# ppt_full_charger_f1.net
KiCad netlist of a schematic drawn in EAGLE
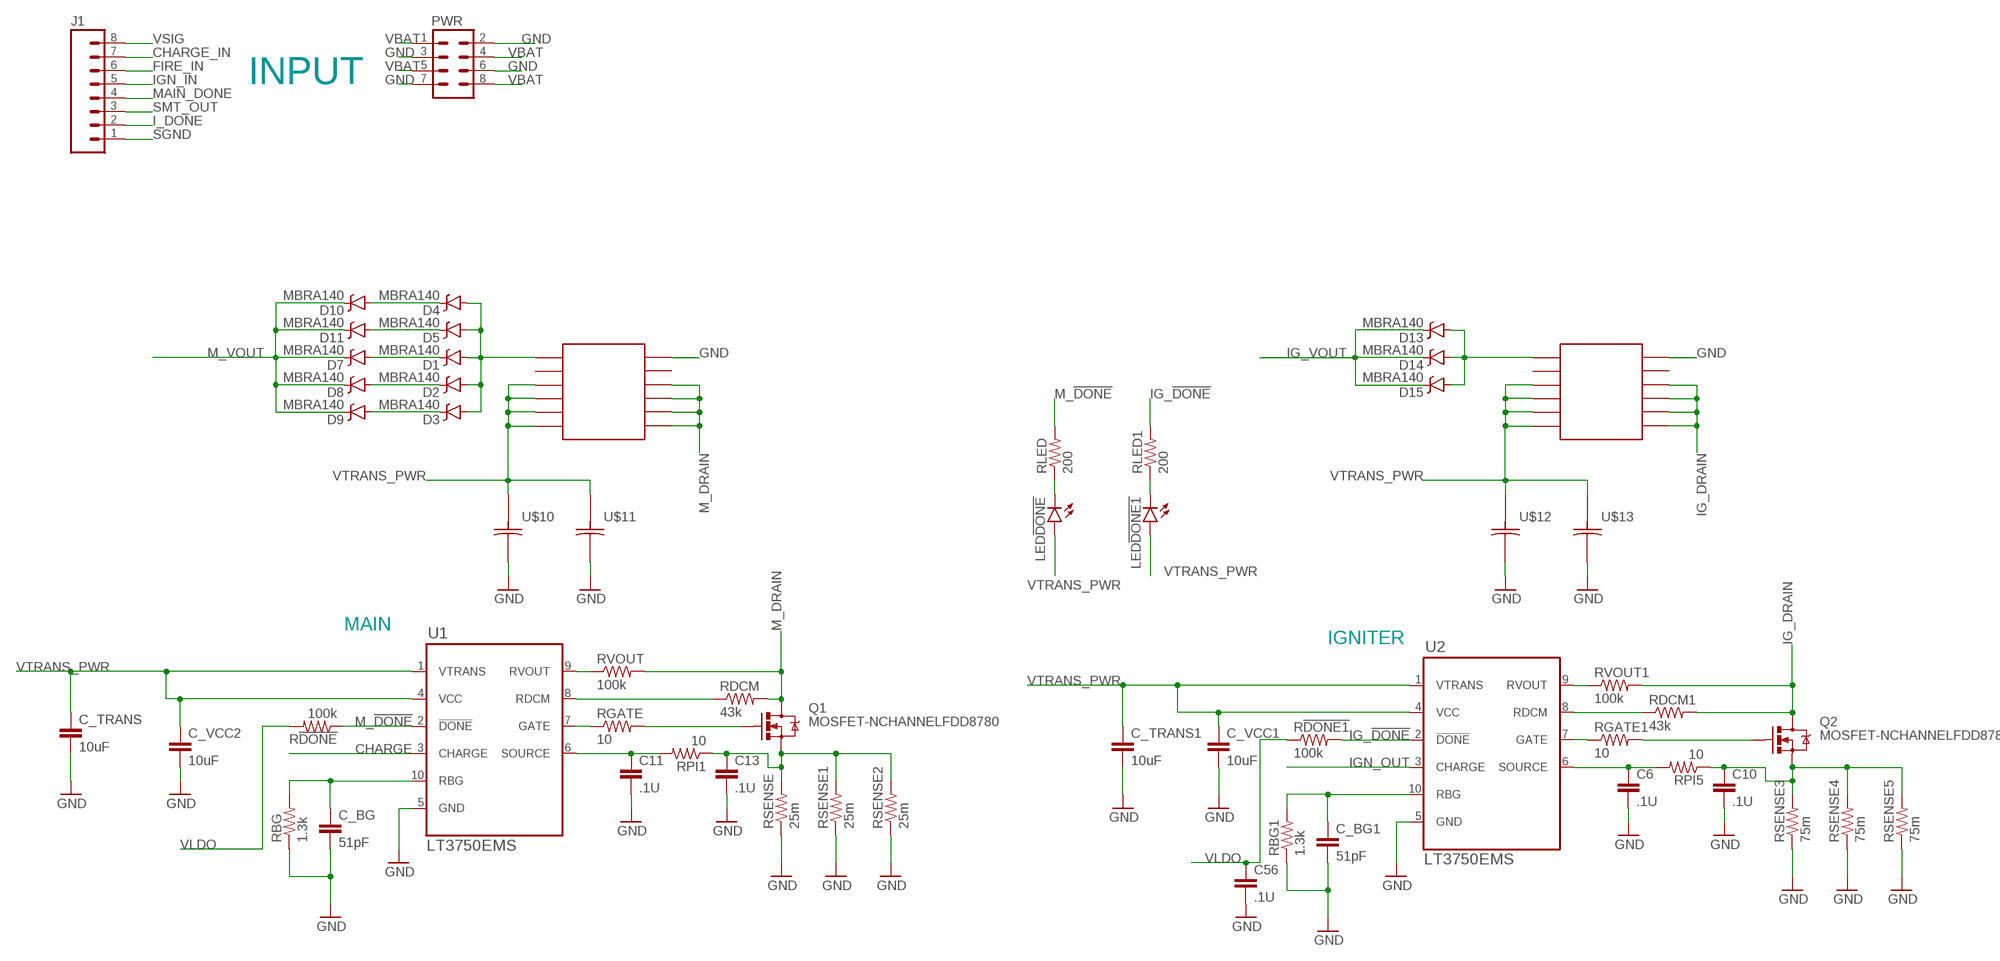
[diagram p0: schematic, sheet 1]
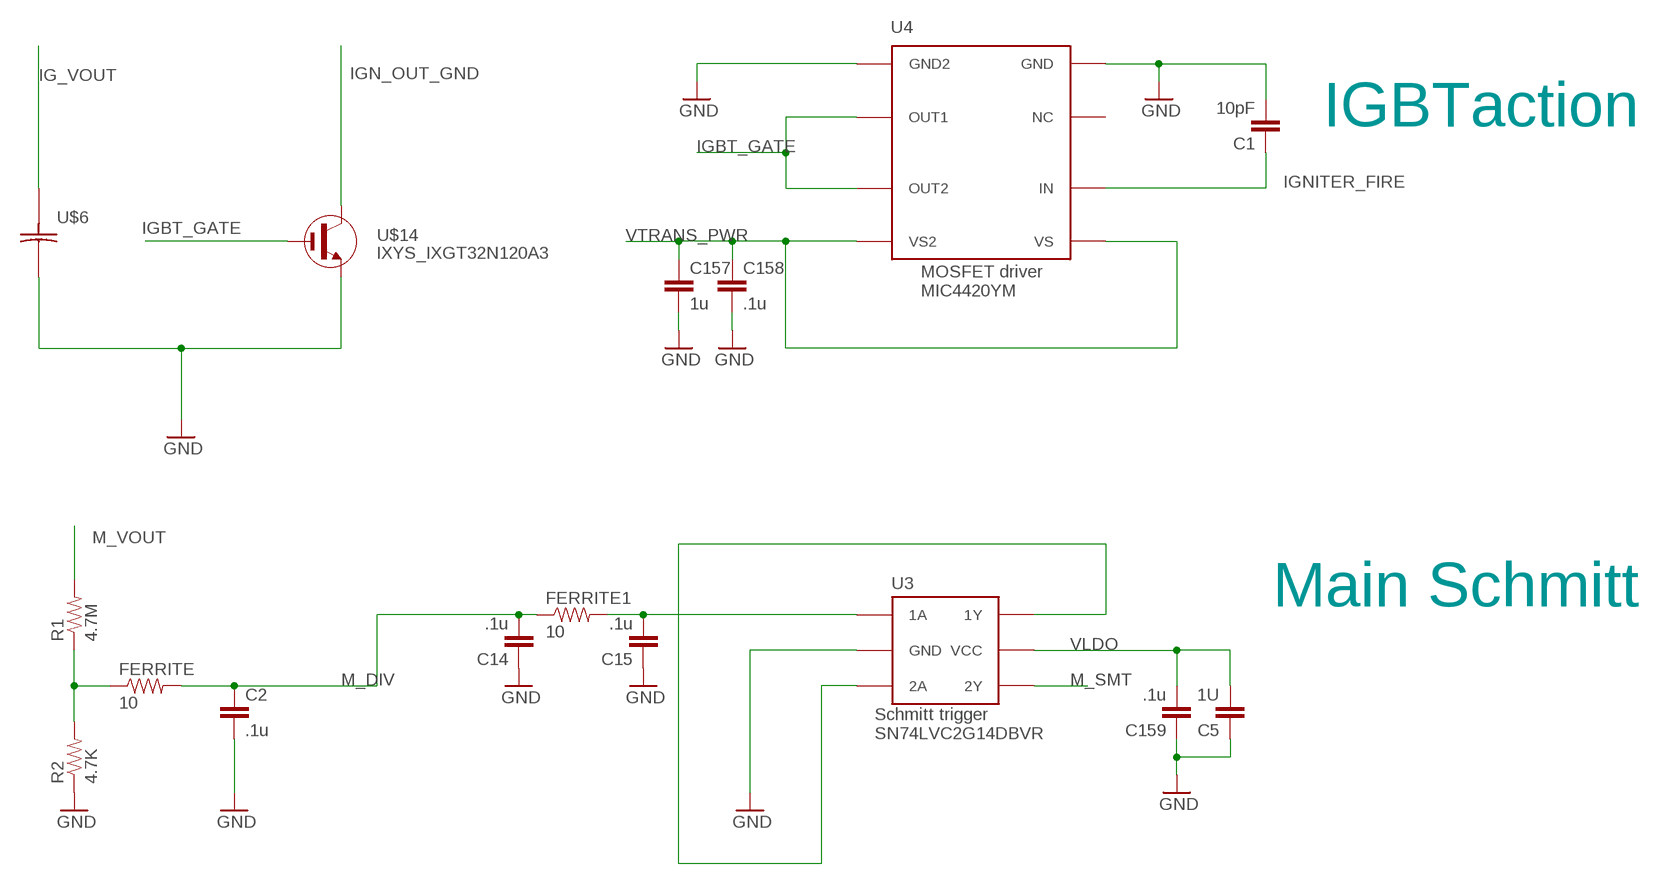
[diagram p1: schematic, sheet 2]
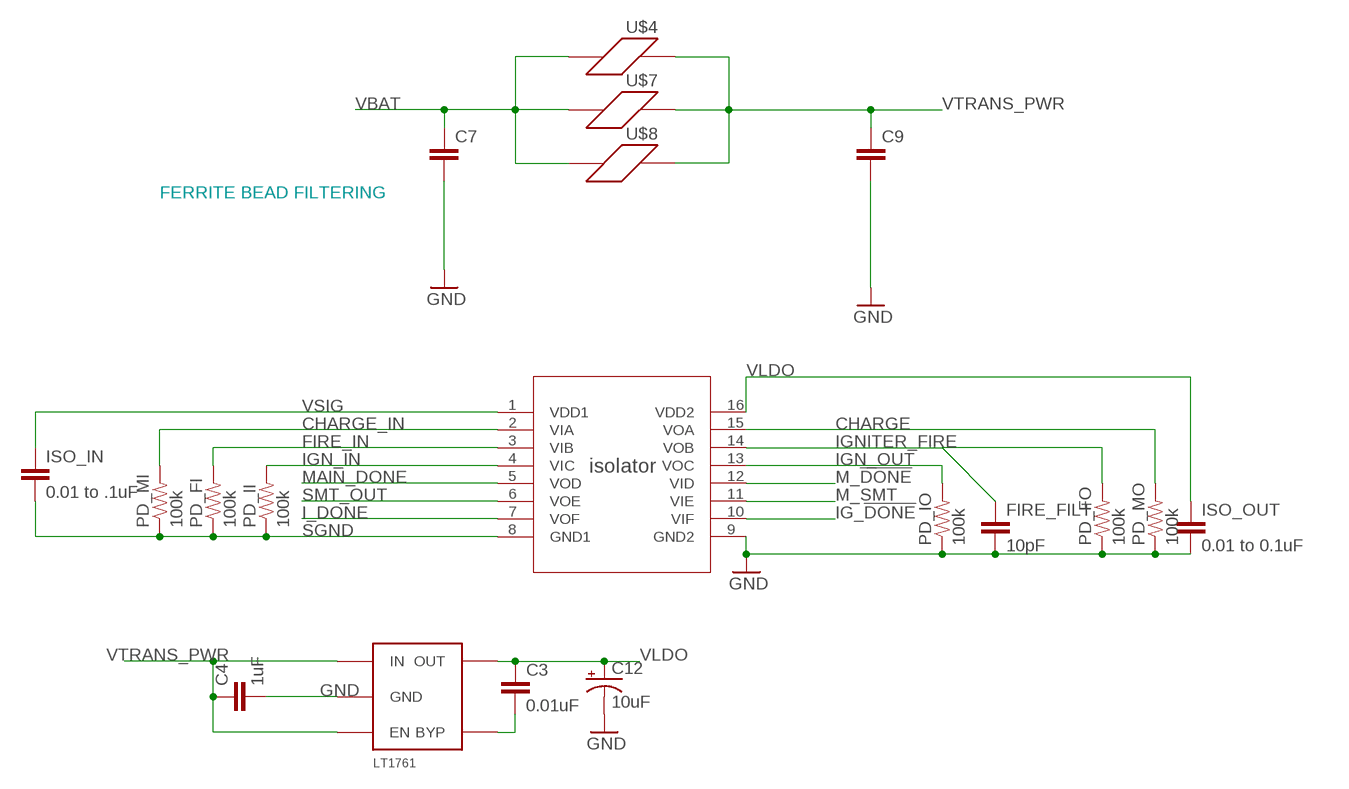
[diagram p2: schematic, sheet 3]

(export (version "E")
  (design (tool "Eeschema 10.0.6"))
  (components
    (comp (ref "ADUM163N")
      (value "ADUM163N1BRZ")
      (footprint "eagle-import:R_16")
      (libsource (lib "eagle-import") (part "ADUM163N1BRZ"))
    )
    (comp (ref "C3")
      (value "0.01uF")
      (footprint "eagle-import:0805")
      (libsource (lib "eagle-import") (part "SparkFun-Passives_CAP0805"))
    )
    (comp (ref "C4")
      (value "1uF")
      (footprint "eagle-import:0805")
      (libsource (lib "eagle-import") (part "SparkFun-Passives_CAP0805"))
    )
    (comp (ref "C7")
      (value "CAP0805")
      (footprint "eagle-import:0805")
      (libsource (lib "eagle-import") (part "CAP0805"))
    )
    (comp (ref "C9")
      (value "CAP0805")
      (footprint "eagle-import:0805")
      (libsource (lib "eagle-import") (part "CAP0805"))
    )
    (comp (ref "C12")
      (value "10uF")
      (footprint "eagle-import:EIA3216")
      (libsource (lib "eagle-import") (part "10UF-TANT"))
    )
    (comp (ref "FIRE_FILT")
      (value "10pF")
      (footprint "eagle-import:0805")
      (libsource (lib "eagle-import") (part "SparkFun-Passives_CAP0805"))
    )
    (comp (ref "ISO_IN")
      (value "0.01 to .1uF")
      (footprint "eagle-import:0805")
      (libsource (lib "eagle-import") (part "SparkFun-Passives_CAP0805"))
    )
    (comp (ref "ISO_OUT")
      (value "0.01 to 0.1uF")
      (footprint "eagle-import:0805")
      (libsource (lib "eagle-import") (part "SparkFun-Passives_CAP0805"))
    )
    (comp (ref "LDO")
      (value "LINEAR_LDO_LT1761-X")
      (footprint "eagle-import:SOT-23-5")
      (libsource (lib "eagle-import") (part "LINEAR_LDO_LT1761-X"))
    )
    (comp (ref "PD_FI")
      (value "100k")
      (footprint "eagle-import:0805")
      (libsource (lib "eagle-import") (part "RESISTOR0805-RES"))
    )
    (comp (ref "PD_FO")
      (value "100k")
      (footprint "eagle-import:0805")
      (libsource (lib "eagle-import") (part "RESISTOR0805-RES"))
    )
    (comp (ref "PD_II")
      (value "100k")
      (footprint "eagle-import:0805")
      (libsource (lib "eagle-import") (part "RESISTOR0805-RES"))
    )
    (comp (ref "PD_IO")
      (value "100k")
      (footprint "eagle-import:0805")
      (libsource (lib "eagle-import") (part "RESISTOR0805-RES"))
    )
    (comp (ref "PD_MI")
      (value "100k")
      (footprint "eagle-import:0805")
      (libsource (lib "eagle-import") (part "RESISTOR0805-RES"))
    )
    (comp (ref "PD_MO")
      (value "100k")
      (footprint "eagle-import:0805")
      (libsource (lib "eagle-import") (part "RESISTOR0805-RES"))
    )
    (comp (ref "U$4")
      (value "B.L1_FBMJ2125HS420-T")
      (footprint "eagle-import:0805")
      (libsource (lib "eagle-import") (part "B.L1_FBMJ2125HS420-T"))
    )
    (comp (ref "U$7")
      (value "B.L2_FBMH1608HL121-T")
      (footprint "eagle-import:0603")
      (libsource (lib "eagle-import") (part "B.L2_FBMH1608HL121-T"))
    )
    (comp (ref "U$8")
      (value "I.L1_587-3855-1-ND")
      (footprint "eagle-import:1206")
      (libsource (lib "eagle-import") (part "I.L1_587-3855-1-ND"))
    )
    (comp (ref "C6")
      (value ".1U")
      (footprint "eagle-import:0805")
      (libsource (lib "eagle-import") (part "CAP0805"))
    )
    (comp (ref "C10")
      (value ".1U")
      (footprint "eagle-import:0805")
      (libsource (lib "eagle-import") (part "CAP0805"))
    )
    (comp (ref "C11")
      (value ".1U")
      (footprint "eagle-import:0805")
      (libsource (lib "eagle-import") (part "CAP0805"))
    )
    (comp (ref "C13")
      (value ".1U")
      (footprint "eagle-import:0805")
      (libsource (lib "eagle-import") (part "CAP0805"))
    )
    (comp (ref "C56")
      (value ".1U")
      (footprint "eagle-import:0805")
      (libsource (lib "eagle-import") (part "CAP0805"))
    )
    (comp (ref "C_BG")
      (value "51pF")
      (footprint "eagle-import:0805")
      (libsource (lib "eagle-import") (part "CAP0805"))
    )
    (comp (ref "C_BG1")
      (value "51pF")
      (footprint "eagle-import:0805")
      (libsource (lib "eagle-import") (part "CAP0805"))
    )
    (comp (ref "C_TRANS")
      (value "10uF")
      (footprint "eagle-import:0805")
      (libsource (lib "eagle-import") (part "CAP0805"))
    )
    (comp (ref "C_TRANS1")
      (value "10uF")
      (footprint "eagle-import:0805")
      (libsource (lib "eagle-import") (part "CAP0805"))
    )
    (comp (ref "C_VCC1")
      (value "10uF")
      (footprint "eagle-import:0805")
      (libsource (lib "eagle-import") (part "CAP0805"))
    )
    (comp (ref "C_VCC2")
      (value "10uF")
      (footprint "eagle-import:0805")
      (libsource (lib "eagle-import") (part "CAP0805"))
    )
    (comp (ref "D1")
      (value "MBRA140")
      (footprint "eagle-import:SMA-DIODE")
      (libsource (lib "eagle-import") (part "MBRA140"))
    )
    (comp (ref "D2")
      (value "MBRA140")
      (footprint "eagle-import:SMA-DIODE")
      (libsource (lib "eagle-import") (part "MBRA140"))
    )
    (comp (ref "D3")
      (value "MBRA140")
      (footprint "eagle-import:SMA-DIODE")
      (libsource (lib "eagle-import") (part "MBRA140"))
    )
    (comp (ref "D4")
      (value "MBRA140")
      (footprint "eagle-import:SMA-DIODE")
      (libsource (lib "eagle-import") (part "MBRA140"))
    )
    (comp (ref "D5")
      (value "MBRA140")
      (footprint "eagle-import:SMA-DIODE")
      (libsource (lib "eagle-import") (part "MBRA140"))
    )
    (comp (ref "D7")
      (value "MBRA140")
      (footprint "eagle-import:SMA-DIODE")
      (libsource (lib "eagle-import") (part "MBRA140"))
    )
    (comp (ref "D8")
      (value "MBRA140")
      (footprint "eagle-import:SMA-DIODE")
      (libsource (lib "eagle-import") (part "MBRA140"))
    )
    (comp (ref "D9")
      (value "MBRA140")
      (footprint "eagle-import:SMA-DIODE")
      (libsource (lib "eagle-import") (part "MBRA140"))
    )
    (comp (ref "D10")
      (value "MBRA140")
      (footprint "eagle-import:SMA-DIODE")
      (libsource (lib "eagle-import") (part "MBRA140"))
    )
    (comp (ref "D11")
      (value "MBRA140")
      (footprint "eagle-import:SMA-DIODE")
      (libsource (lib "eagle-import") (part "MBRA140"))
    )
    (comp (ref "D13")
      (value "MBRA140")
      (footprint "eagle-import:SMA-DIODE")
      (libsource (lib "eagle-import") (part "MBRA140"))
    )
    (comp (ref "D14")
      (value "MBRA140")
      (footprint "eagle-import:SMA-DIODE")
      (libsource (lib "eagle-import") (part "MBRA140"))
    )
    (comp (ref "D15")
      (value "MBRA140")
      (footprint "eagle-import:SMA-DIODE")
      (libsource (lib "eagle-import") (part "MBRA140"))
    )
    (comp (ref "J1")
      (value "M08")
      (footprint "eagle-import:1X08_ROUND")
      (libsource (lib "eagle-import") (part "M08"))
    )
    (comp (ref "LED!DONE")
      (value "LED1206")
      (footprint "eagle-import:LED-1206")
      (libsource (lib "eagle-import") (part "LED1206"))
    )
    (comp (ref "LED!DONE1")
      (value "LED1206")
      (footprint "eagle-import:LED-1206")
      (libsource (lib "eagle-import") (part "LED1206"))
    )
    (comp (ref "PWR")
      (value "M04X2")
      (footprint "eagle-import:2X4")
      (libsource (lib "eagle-import") (part "M04X2"))
    )
    (comp (ref "Q1")
      (value "MOSFET-NCHANNELFDD8780")
      (footprint "eagle-import:DPAK")
      (libsource (lib "eagle-import") (part "MOSFET-NCHANNELFDD8780"))
    )
    (comp (ref "Q2")
      (value "MOSFET-NCHANNELFDD8780")
      (footprint "eagle-import:DPAK")
      (libsource (lib "eagle-import") (part "MOSFET-NCHANNELFDD8780"))
    )
    (comp (ref "R!DONE")
      (value "100k")
      (footprint "eagle-import:0805")
      (libsource (lib "eagle-import") (part "SparkFun-Resistors_RESISTOR0805-RES"))
    )
    (comp (ref "R!DONE1")
      (value "100k")
      (footprint "eagle-import:0805")
      (libsource (lib "eagle-import") (part "SparkFun-Resistors_RESISTOR0805-RES"))
    )
    (comp (ref "RBG")
      (value "1.3k")
      (footprint "eagle-import:0805")
      (libsource (lib "eagle-import") (part "SparkFun-Resistors_RESISTOR0805-RES"))
    )
    (comp (ref "RBG1")
      (value "1.3k")
      (footprint "eagle-import:0805")
      (libsource (lib "eagle-import") (part "SparkFun-Resistors_RESISTOR0805-RES"))
    )
    (comp (ref "RDCM")
      (value "43k")
      (footprint "eagle-import:0805")
      (libsource (lib "eagle-import") (part "SparkFun-Resistors_RESISTOR0805-RES"))
    )
    (comp (ref "RDCM1")
      (value "43k")
      (footprint "eagle-import:0805")
      (libsource (lib "eagle-import") (part "SparkFun-Resistors_RESISTOR0805-RES"))
    )
    (comp (ref "RGATE")
      (value "10")
      (footprint "eagle-import:0805")
      (libsource (lib "eagle-import") (part "SparkFun-Resistors_RESISTOR0805-RES"))
    )
    (comp (ref "RGATE1")
      (value "10")
      (footprint "eagle-import:0805")
      (libsource (lib "eagle-import") (part "SparkFun-Resistors_RESISTOR0805-RES"))
    )
    (comp (ref "RLED")
      (value "200")
      (footprint "eagle-import:0805")
      (libsource (lib "eagle-import") (part "RESISTOR0805-RES"))
    )
    (comp (ref "RLED1")
      (value "200")
      (footprint "eagle-import:0805")
      (libsource (lib "eagle-import") (part "RESISTOR0805-RES"))
    )
    (comp (ref "RPI1")
      (value "10")
      (footprint "eagle-import:0805")
      (libsource (lib "eagle-import") (part "SparkFun-Resistors_RESISTOR0805-RES"))
    )
    (comp (ref "RPI5")
      (value "10")
      (footprint "eagle-import:0805")
      (libsource (lib "eagle-import") (part "SparkFun-Resistors_RESISTOR0805-RES"))
    )
    (comp (ref "RSENSE")
      (value "25m")
      (footprint "eagle-import:1206")
      (libsource (lib "eagle-import") (part "RESISTOR1206"))
    )
    (comp (ref "RSENSE1")
      (value "25m")
      (footprint "eagle-import:1206")
      (libsource (lib "eagle-import") (part "RESISTOR1206"))
    )
    (comp (ref "RSENSE2")
      (value "25m")
      (footprint "eagle-import:1206")
      (libsource (lib "eagle-import") (part "RESISTOR1206"))
    )
    (comp (ref "RSENSE3")
      (value "75m")
      (footprint "eagle-import:1206")
      (libsource (lib "eagle-import") (part "RESISTOR1206"))
    )
    (comp (ref "RSENSE4")
      (value "75m")
      (footprint "eagle-import:1206")
      (libsource (lib "eagle-import") (part "RESISTOR1206"))
    )
    (comp (ref "RSENSE5")
      (value "75m")
      (footprint "eagle-import:1206")
      (libsource (lib "eagle-import") (part "RESISTOR1206"))
    )
    (comp (ref "RVOUT")
      (value "100k")
      (footprint "eagle-import:0805")
      (libsource (lib "eagle-import") (part "SparkFun-Resistors_RESISTOR0805-RES"))
    )
    (comp (ref "RVOUT1")
      (value "100k")
      (footprint "eagle-import:0805")
      (libsource (lib "eagle-import") (part "SparkFun-Resistors_RESISTOR0805-RES"))
    )
    (comp (ref "U$1")
      (value "COILCRAFT_DA2034")
      (footprint "eagle-import:DA2034")
      (libsource (lib "eagle-import") (part "COILCRAFT_DA2034"))
    )
    (comp (ref "U$2")
      (value "COILCRAFT_DA2033")
      (footprint "eagle-import:DA2033")
      (libsource (lib "eagle-import") (part "COILCRAFT_DA2033"))
    )
    (comp (ref "U$10")
      (value "PANASONIC_16SVPG270M")
      (footprint "eagle-import:PANASONIC_SVPG")
      (libsource (lib "eagle-import") (part "PANASONIC_16SVPG270M"))
    )
    (comp (ref "U$11")
      (value "PANASONIC_16SVPG270M")
      (footprint "eagle-import:PANASONIC_SVPG")
      (libsource (lib "eagle-import") (part "PANASONIC_16SVPG270M"))
    )
    (comp (ref "U$12")
      (value "PANASONIC_16SVPG270M")
      (footprint "eagle-import:PANASONIC_SVPG")
      (libsource (lib "eagle-import") (part "PANASONIC_16SVPG270M"))
    )
    (comp (ref "U$13")
      (value "PANASONIC_16SVPG270M")
      (footprint "eagle-import:PANASONIC_SVPG")
      (libsource (lib "eagle-import") (part "PANASONIC_16SVPG270M"))
    )
    (comp (ref "U1")
      (value "LT3750EMS")
      (footprint "eagle-import:MSOP10")
      (libsource (lib "eagle-import") (part "LT3750EMS"))
    )
    (comp (ref "U2")
      (value "LT3750EMS")
      (footprint "eagle-import:MSOP10")
      (libsource (lib "eagle-import") (part "LT3750EMS"))
    )
    (comp (ref "C1")
      (value "10pF")
      (footprint "eagle-import:0805")
      (libsource (lib "eagle-import") (part "CAP0805"))
    )
    (comp (ref "C2")
      (value ".1u")
      (footprint "eagle-import:0805")
      (libsource (lib "eagle-import") (part "CAP0805"))
    )
    (comp (ref "C5")
      (value "1U")
      (footprint "eagle-import:0805")
      (libsource (lib "eagle-import") (part "CAP0805"))
    )
    (comp (ref "C14")
      (value ".1u")
      (footprint "eagle-import:0805")
      (libsource (lib "eagle-import") (part "CAP0805"))
    )
    (comp (ref "C15")
      (value ".1u")
      (footprint "eagle-import:0805")
      (libsource (lib "eagle-import") (part "CAP0805"))
    )
    (comp (ref "C157")
      (value "1u")
      (footprint "eagle-import:0805")
      (libsource (lib "eagle-import") (part "CAP0805"))
    )
    (comp (ref "C158")
      (value ".1u")
      (footprint "eagle-import:0805")
      (libsource (lib "eagle-import") (part "CAP0805"))
    )
    (comp (ref "C159")
      (value ".1u")
      (footprint "eagle-import:0805")
      (libsource (lib "eagle-import") (part "CAP0805"))
    )
    (comp (ref "FERRITE")
      (value "10")
      (footprint "eagle-import:0805")
      (libsource (lib "eagle-import") (part "RESISTOR0805-RES"))
    )
    (comp (ref "FERRITE1")
      (value "10")
      (footprint "eagle-import:0805")
      (libsource (lib "eagle-import") (part "RESISTOR0805-RES"))
    )
    (comp (ref "R1")
      (value "4.7M")
      (footprint "eagle-import:R2010")
      (libsource (lib "eagle-import") (part "SparkFun-Passives_RESISTOR2010"))
    )
    (comp (ref "R2")
      (value "4.7K")
      (footprint "eagle-import:R2010")
      (libsource (lib "eagle-import") (part "SparkFun-Passives_RESISTOR2010"))
    )
    (comp (ref "U$6")
      (value "KEMET_LDEQH3100KA5N00")
      (footprint "eagle-import:KEMET_F3078")
      (libsource (lib "eagle-import") (part "KEMET_LDEQH3100KA5N00"))
    )
    (comp (ref "U$14")
      (value "IXYS_IXGT32N120A3")
      (footprint "eagle-import:TO-268")
      (libsource (lib "eagle-import") (part "IXYS_IXGT32N120A3"))
    )
    (comp (ref "U3")
      (value "TI_SCHMITTRIGGER_SN74")
      (footprint "eagle-import:SOT-23-6")
      (libsource (lib "eagle-import") (part "TI_SCHMITTRIGGER_SN74"))
    )
    (comp (ref "U4")
      (value "MICREL_MOSFETDRIVER_MIC4420")
      (footprint "eagle-import:8-SOIC")
      (libsource (lib "eagle-import") (part "MICREL_MOSFETDRIVER_MIC4420"))
    )
  )
  (nets
    (net (code "1") (name "CHARGE") (class "Default")
      (node (ref "ADUM163N") (pin "15") (pinfunction "VOA_15") (pintype "passive"))
      (node (ref "PD_MO") (pin "2") (pinfunction "2_2") (pintype "passive"))
      (node (ref "U1") (pin "3") (pinfunction "CHARGE_3") (pintype "bidirectional"))
    )
    (net (code "2") (name "CHARGE_IN") (class "Default")
      (node (ref "ADUM163N") (pin "2") (pinfunction "VIA_2") (pintype "passive"))
      (node (ref "J1") (pin "7") (pinfunction "7_7") (pintype "passive"))
      (node (ref "PD_MI") (pin "2") (pinfunction "2_2") (pintype "passive"))
    )
    (net (code "3") (name "FIRE_IN") (class "Default")
      (node (ref "ADUM163N") (pin "3") (pinfunction "VIB_3") (pintype "passive"))
      (node (ref "J1") (pin "6") (pinfunction "6_6") (pintype "passive"))
      (node (ref "PD_FI") (pin "2") (pinfunction "2_2") (pintype "passive"))
    )
    (net (code "4") (name "GND") (class "Default")
      (node (ref "ADUM163N") (pin "9") (pinfunction "GND2_9") (pintype "passive"))
      (node (ref "C1") (pin "2") (pinfunction "2_2") (pintype "passive"))
      (node (ref "C10") (pin "2") (pinfunction "2_2") (pintype "passive"))
      (node (ref "C11") (pin "2") (pinfunction "2_2") (pintype "passive"))
      (node (ref "C12") (pin "C") (pinfunction "-_C") (pintype "passive"))
      (node (ref "C13") (pin "2") (pinfunction "2_2") (pintype "passive"))
      (node (ref "C14") (pin "1") (pinfunction "1_1") (pintype "passive"))
      (node (ref "C15") (pin "1") (pinfunction "1_1") (pintype "passive"))
      (node (ref "C157") (pin "2") (pinfunction "2_2") (pintype "passive"))
      (node (ref "C158") (pin "2") (pinfunction "2_2") (pintype "passive"))
      (node (ref "C159") (pin "1") (pinfunction "1_1") (pintype "passive"))
      (node (ref "C2") (pin "2") (pinfunction "2_2") (pintype "passive"))
      (node (ref "C4") (pin "2") (pinfunction "2_2") (pintype "passive"))
      (node (ref "C5") (pin "1") (pinfunction "1_1") (pintype "passive"))
      (node (ref "C56") (pin "2") (pinfunction "2_2") (pintype "passive"))
      (node (ref "C6") (pin "2") (pinfunction "2_2") (pintype "passive"))
      (node (ref "C7") (pin "2") (pinfunction "2_2") (pintype "passive"))
      (node (ref "C9") (pin "2") (pinfunction "2_2") (pintype "passive"))
      (node (ref "C_BG") (pin "2") (pinfunction "2_2") (pintype "passive"))
      (node (ref "C_BG1") (pin "2") (pinfunction "2_2") (pintype "passive"))
      (node (ref "C_TRANS") (pin "2") (pinfunction "2_2") (pintype "passive"))
      (node (ref "C_TRANS1") (pin "2") (pinfunction "2_2") (pintype "passive"))
      (node (ref "C_VCC1") (pin "2") (pinfunction "2_2") (pintype "passive"))
      (node (ref "C_VCC2") (pin "2") (pinfunction "2_2") (pintype "passive"))
      (node (ref "FIRE_FILT") (pin "2") (pinfunction "2_2") (pintype "passive"))
      (node (ref "ISO_OUT") (pin "2") (pinfunction "2_2") (pintype "passive"))
      (node (ref "LDO") (pin "P$2") (pinfunction "GND_P$2") (pintype "bidirectional"))
      (node (ref "PD_FO") (pin "1") (pinfunction "1_1") (pintype "passive"))
      (node (ref "PD_IO") (pin "1") (pinfunction "1_1") (pintype "passive"))
      (node (ref "PD_MO") (pin "1") (pinfunction "1_1") (pintype "passive"))
      (node (ref "PWR") (pin "2") (pinfunction "2_2") (pintype "passive"))
      (node (ref "PWR") (pin "3") (pinfunction "3_3") (pintype "passive"))
      (node (ref "PWR") (pin "6") (pinfunction "6_6") (pintype "passive"))
      (node (ref "PWR") (pin "7") (pinfunction "7_7") (pintype "passive"))
      (node (ref "R2") (pin "1") (pinfunction "1_1") (pintype "passive"))
      (node (ref "RBG") (pin "1") (pinfunction "1_1") (pintype "passive"))
      (node (ref "RBG1") (pin "1") (pinfunction "1_1") (pintype "passive"))
      (node (ref "RSENSE") (pin "1") (pinfunction "1_1") (pintype "passive"))
      (node (ref "RSENSE1") (pin "1") (pinfunction "1_1") (pintype "passive"))
      (node (ref "RSENSE2") (pin "1") (pinfunction "1_1") (pintype "passive"))
      (node (ref "RSENSE3") (pin "1") (pinfunction "1_1") (pintype "passive"))
      (node (ref "RSENSE4") (pin "1") (pinfunction "1_1") (pintype "passive"))
      (node (ref "RSENSE5") (pin "1") (pinfunction "1_1") (pintype "passive"))
      (node (ref "U$1") (pin "P$12") (pinfunction "P$12_P$12") (pintype "bidirectional"))
      (node (ref "U$10") (pin "NEG") (pinfunction "NEG_NEG") (pintype "bidirectional"))
      (node (ref "U$11") (pin "NEG") (pinfunction "NEG_NEG") (pintype "bidirectional"))
      (node (ref "U$12") (pin "NEG") (pinfunction "NEG_NEG") (pintype "bidirectional"))
      (node (ref "U$13") (pin "NEG") (pinfunction "NEG_NEG") (pintype "bidirectional"))
      (node (ref "U$14") (pin "3") (pinfunction "E_3") (pintype "passive"))
      (node (ref "U$2") (pin "P$12") (pinfunction "P$12_P$12") (pintype "bidirectional"))
      (node (ref "U$6") (pin "NEG") (pinfunction "NEG_NEG") (pintype "bidirectional"))
      (node (ref "U1") (pin "5") (pinfunction "GND_5") (pintype "passive"))
      (node (ref "U2") (pin "5") (pinfunction "GND_5") (pintype "passive"))
      (node (ref "U3") (pin "P$2") (pinfunction "GND_P$2") (pintype "bidirectional"))
      (node (ref "U4") (pin "P$4") (pinfunction "GND_P$4") (pintype "bidirectional"))
      (node (ref "U4") (pin "P$5") (pinfunction "GND2_P$5") (pintype "bidirectional"))
    )
    (net (code "5") (name "IGBT_GATE") (class "Default")
      (node (ref "U$14") (pin "1") (pinfunction "G_1") (pintype "passive"))
      (node (ref "U4") (pin "P$6") (pinfunction "OUT1_P$6") (pintype "bidirectional"))
      (node (ref "U4") (pin "P$7") (pinfunction "OUT2_P$7") (pintype "bidirectional"))
    )
    (net (code "6") (name "IGNITER_FIRE") (class "Default")
      (node (ref "ADUM163N") (pin "14") (pinfunction "VOB_14") (pintype "passive"))
      (node (ref "C1") (pin "1") (pinfunction "1_1") (pintype "passive"))
      (node (ref "FIRE_FILT") (pin "1") (pinfunction "1_1") (pintype "passive"))
      (node (ref "PD_FO") (pin "2") (pinfunction "2_2") (pintype "passive"))
      (node (ref "U4") (pin "P$2") (pinfunction "IN_P$2") (pintype "bidirectional"))
    )
    (net (code "7") (name "IGN_IN") (class "Default")
      (node (ref "ADUM163N") (pin "4") (pinfunction "VIC_4") (pintype "passive"))
      (node (ref "J1") (pin "5") (pinfunction "5_5") (pintype "passive"))
      (node (ref "PD_II") (pin "2") (pinfunction "2_2") (pintype "passive"))
    )
    (net (code "8") (name "IGN_OUT") (class "Default")
      (node (ref "ADUM163N") (pin "13") (pinfunction "VOC_13") (pintype "passive"))
      (node (ref "PD_IO") (pin "2") (pinfunction "2_2") (pintype "passive"))
      (node (ref "U2") (pin "3") (pinfunction "CHARGE_3") (pintype "bidirectional"))
    )
    (net (code "9") (name "IGN_OUT_GND") (class "Default")
      (node (ref "U$14") (pin "2") (pinfunction "C_2") (pintype "passive"))
    )
    (net (code "10") (name "IG_DRAIN") (class "Default")
      (node (ref "Q2") (pin "4") (pinfunction "D_4") (pintype "passive"))
      (node (ref "RDCM1") (pin "2") (pinfunction "2_2") (pintype "passive"))
      (node (ref "RVOUT1") (pin "2") (pinfunction "2_2") (pintype "passive"))
      (node (ref "U$2") (pin "P$10") (pinfunction "P$10_P$10") (pintype "bidirectional"))
      (node (ref "U$2") (pin "P$7") (pinfunction "P$7_P$7") (pintype "bidirectional"))
      (node (ref "U$2") (pin "P$8") (pinfunction "P$8_P$8") (pintype "bidirectional"))
      (node (ref "U$2") (pin "P$9") (pinfunction "P$9_P$9") (pintype "bidirectional"))
    )
    (net (code "11") (name "IG_VOUT") (class "Default")
      (node (ref "D13") (pin "C") (pinfunction "C_C") (pintype "passive"))
      (node (ref "D14") (pin "C") (pinfunction "C_C") (pintype "passive"))
      (node (ref "D15") (pin "C") (pinfunction "C_C") (pintype "passive"))
      (node (ref "U$6") (pin "POS") (pinfunction "POS_POS") (pintype "bidirectional"))
    )
    (net (code "12") (name "IG_~{DONE}") (class "Default")
      (node (ref "ADUM163N") (pin "10") (pinfunction "VIF_10") (pintype "passive"))
      (node (ref "R!DONE1") (pin "2") (pinfunction "2_2") (pintype "passive"))
      (node (ref "RLED1") (pin "2") (pinfunction "2_2") (pintype "passive"))
      (node (ref "U2") (pin "2") (pinfunction "~{DONE}_2") (pintype "bidirectional"))
    )
    (net (code "13") (name "I_DONE") (class "Default")
      (node (ref "ADUM163N") (pin "7") (pinfunction "VOF_7") (pintype "passive"))
      (node (ref "J1") (pin "2") (pinfunction "2_2") (pintype "passive"))
    )
    (net (code "14") (name "MAIN_DONE") (class "Default")
      (node (ref "ADUM163N") (pin "5") (pinfunction "VOD_5") (pintype "passive"))
      (node (ref "J1") (pin "4") (pinfunction "4_4") (pintype "passive"))
    )
    (net (code "15") (name "M_DIV") (class "Default")
      (node (ref "C14") (pin "2") (pinfunction "2_2") (pintype "passive"))
      (node (ref "C2") (pin "1") (pinfunction "1_1") (pintype "passive"))
      (node (ref "FERRITE") (pin "2") (pinfunction "2_2") (pintype "passive"))
      (node (ref "FERRITE1") (pin "1") (pinfunction "1_1") (pintype "passive"))
    )
    (net (code "16") (name "M_DRAIN") (class "Default")
      (node (ref "Q1") (pin "4") (pinfunction "D_4") (pintype "passive"))
      (node (ref "RDCM") (pin "2") (pinfunction "2_2") (pintype "passive"))
      (node (ref "RVOUT") (pin "2") (pinfunction "2_2") (pintype "passive"))
      (node (ref "U$1") (pin "P$10") (pinfunction "P$10_P$10") (pintype "bidirectional"))
      (node (ref "U$1") (pin "P$7") (pinfunction "P$7_P$7") (pintype "bidirectional"))
      (node (ref "U$1") (pin "P$8") (pinfunction "P$8_P$8") (pintype "bidirectional"))
      (node (ref "U$1") (pin "P$9") (pinfunction "P$9_P$9") (pintype "bidirectional"))
    )
    (net (code "17") (name "M_SMT") (class "Default")
      (node (ref "ADUM163N") (pin "11") (pinfunction "VIE_11") (pintype "passive"))
      (node (ref "U3") (pin "P$4") (pinfunction "2Y_P$4") (pintype "bidirectional"))
    )
    (net (code "18") (name "M_VOUT") (class "Default")
      (node (ref "D10") (pin "C") (pinfunction "C_C") (pintype "passive"))
      (node (ref "D11") (pin "C") (pinfunction "C_C") (pintype "passive"))
      (node (ref "D7") (pin "C") (pinfunction "C_C") (pintype "passive"))
      (node (ref "D8") (pin "C") (pinfunction "C_C") (pintype "passive"))
      (node (ref "D9") (pin "C") (pinfunction "C_C") (pintype "passive"))
      (node (ref "R1") (pin "2") (pinfunction "2_2") (pintype "passive"))
    )
    (net (code "19") (name "M_~{DONE}") (class "Default")
      (node (ref "ADUM163N") (pin "12") (pinfunction "VID_12") (pintype "passive"))
      (node (ref "R!DONE") (pin "1") (pinfunction "1_1") (pintype "passive"))
      (node (ref "RLED") (pin "2") (pinfunction "2_2") (pintype "passive"))
      (node (ref "U1") (pin "2") (pinfunction "~{DONE}_2") (pintype "bidirectional"))
    )
    (net (code "20") (name "Net-(D1-PadA)") (class "Default")
      (node (ref "D1") (pin "A") (pinfunction "A_A") (pintype "passive"))
      (node (ref "D2") (pin "A") (pinfunction "A_A") (pintype "passive"))
      (node (ref "D3") (pin "A") (pinfunction "A_A") (pintype "passive"))
      (node (ref "D4") (pin "A") (pinfunction "A_A") (pintype "passive"))
      (node (ref "D5") (pin "A") (pinfunction "A_A") (pintype "passive"))
      (node (ref "U$1") (pin "P$1") (pinfunction "P$1_P$1") (pintype "bidirectional"))
    )
    (net (code "21") (name "Net-(D1-PadC)") (class "Default")
      (node (ref "D1") (pin "C") (pinfunction "C_C") (pintype "passive"))
      (node (ref "D7") (pin "A") (pinfunction "A_A") (pintype "passive"))
    )
    (net (code "22") (name "Net-(D2-PadC)") (class "Default")
      (node (ref "D2") (pin "C") (pinfunction "C_C") (pintype "passive"))
      (node (ref "D8") (pin "A") (pinfunction "A_A") (pintype "passive"))
    )
    (net (code "23") (name "Net-(D3-PadC)") (class "Default")
      (node (ref "D3") (pin "C") (pinfunction "C_C") (pintype "passive"))
      (node (ref "D9") (pin "A") (pinfunction "A_A") (pintype "passive"))
    )
    (net (code "24") (name "Net-(D10-PadA)") (class "Default")
      (node (ref "D10") (pin "A") (pinfunction "A_A") (pintype "passive"))
      (node (ref "D4") (pin "C") (pinfunction "C_C") (pintype "passive"))
    )
    (net (code "25") (name "Net-(D11-PadA)") (class "Default")
      (node (ref "D11") (pin "A") (pinfunction "A_A") (pintype "passive"))
      (node (ref "D5") (pin "C") (pinfunction "C_C") (pintype "passive"))
    )
    (net (code "26") (name "Net-(D13-PadA)") (class "Default")
      (node (ref "D13") (pin "A") (pinfunction "A_A") (pintype "passive"))
      (node (ref "D14") (pin "A") (pinfunction "A_A") (pintype "passive"))
      (node (ref "D15") (pin "A") (pinfunction "A_A") (pintype "passive"))
      (node (ref "U$2") (pin "P$1") (pinfunction "P$1_P$1") (pintype "bidirectional"))
    )
    (net (code "27") (name "Net-(FERRITE-Pad1)") (class "Default")
      (node (ref "FERRITE") (pin "1") (pinfunction "1_1") (pintype "passive"))
      (node (ref "R1") (pin "1") (pinfunction "1_1") (pintype "passive"))
      (node (ref "R2") (pin "2") (pinfunction "2_2") (pintype "passive"))
    )
    (net (code "28") (name "Net-(LDO-BYP)") (class "Default")
      (node (ref "C3") (pin "2") (pinfunction "2_2") (pintype "passive"))
      (node (ref "LDO") (pin "P$4") (pinfunction "BYP_P$4") (pintype "bidirectional"))
    )
    (net (code "29") (name "Net-(LED!DONE-PadC)") (class "Default")
      (node (ref "LED!DONE") (pin "C") (pinfunction "C_C") (pintype "passive"))
      (node (ref "RLED") (pin "1") (pinfunction "1_1") (pintype "passive"))
    )
    (net (code "30") (name "Net-(LED!DONE1-PadC)") (class "Default")
      (node (ref "LED!DONE1") (pin "C") (pinfunction "C_C") (pintype "passive"))
      (node (ref "RLED1") (pin "1") (pinfunction "1_1") (pintype "passive"))
    )
    (net (code "31") (name "Net-(Q1-G)") (class "Default")
      (node (ref "Q1") (pin "1") (pinfunction "G_1") (pintype "passive"))
      (node (ref "RGATE") (pin "2") (pinfunction "2_2") (pintype "passive"))
    )
    (net (code "32") (name "Net-(Q1-S)") (class "Default")
      (node (ref "C13") (pin "1") (pinfunction "1_1") (pintype "passive"))
      (node (ref "Q1") (pin "3") (pinfunction "S_3") (pintype "passive"))
      (node (ref "RPI1") (pin "1") (pinfunction "1_1") (pintype "passive"))
      (node (ref "RSENSE") (pin "2") (pinfunction "2_2") (pintype "passive"))
      (node (ref "RSENSE1") (pin "2") (pinfunction "2_2") (pintype "passive"))
      (node (ref "RSENSE2") (pin "2") (pinfunction "2_2") (pintype "passive"))
    )
    (net (code "33") (name "Net-(Q2-G)") (class "Default")
      (node (ref "Q2") (pin "1") (pinfunction "G_1") (pintype "passive"))
      (node (ref "RGATE1") (pin "2") (pinfunction "2_2") (pintype "passive"))
    )
    (net (code "34") (name "Net-(Q2-S)") (class "Default")
      (node (ref "C10") (pin "1") (pinfunction "1_1") (pintype "passive"))
      (node (ref "Q2") (pin "3") (pinfunction "S_3") (pintype "passive"))
      (node (ref "RPI5") (pin "1") (pinfunction "1_1") (pintype "passive"))
      (node (ref "RSENSE3") (pin "2") (pinfunction "2_2") (pintype "passive"))
      (node (ref "RSENSE4") (pin "2") (pinfunction "2_2") (pintype "passive"))
      (node (ref "RSENSE5") (pin "2") (pinfunction "2_2") (pintype "passive"))
    )
    (net (code "35") (name "Net-(U1-GATE)") (class "Default")
      (node (ref "RGATE") (pin "1") (pinfunction "1_1") (pintype "passive"))
      (node (ref "U1") (pin "7") (pinfunction "GATE_7") (pintype "bidirectional"))
    )
    (net (code "36") (name "Net-(U1-RBG)") (class "Default")
      (node (ref "C_BG") (pin "1") (pinfunction "1_1") (pintype "passive"))
      (node (ref "RBG") (pin "2") (pinfunction "2_2") (pintype "passive"))
      (node (ref "U1") (pin "10") (pinfunction "RBG_10") (pintype "output"))
    )
    (net (code "37") (name "Net-(U1-RDCM)") (class "Default")
      (node (ref "RDCM") (pin "1") (pinfunction "1_1") (pintype "passive"))
      (node (ref "U1") (pin "8") (pinfunction "RDCM_8") (pintype "input"))
    )
    (net (code "38") (name "Net-(U1-RVOUT)") (class "Default")
      (node (ref "RVOUT") (pin "1") (pinfunction "1_1") (pintype "passive"))
      (node (ref "U1") (pin "9") (pinfunction "RVOUT_9") (pintype "output"))
    )
    (net (code "39") (name "Net-(U1-SOURCE)") (class "Default")
      (node (ref "C11") (pin "1") (pinfunction "1_1") (pintype "passive"))
      (node (ref "RPI1") (pin "2") (pinfunction "2_2") (pintype "passive"))
      (node (ref "U1") (pin "6") (pinfunction "SOURCE_6") (pintype "input"))
    )
    (net (code "40") (name "Net-(U2-GATE)") (class "Default")
      (node (ref "RGATE1") (pin "1") (pinfunction "1_1") (pintype "passive"))
      (node (ref "U2") (pin "7") (pinfunction "GATE_7") (pintype "bidirectional"))
    )
    (net (code "41") (name "Net-(U2-RBG)") (class "Default")
      (node (ref "C_BG1") (pin "1") (pinfunction "1_1") (pintype "passive"))
      (node (ref "RBG1") (pin "2") (pinfunction "2_2") (pintype "passive"))
      (node (ref "U2") (pin "10") (pinfunction "RBG_10") (pintype "output"))
    )
    (net (code "42") (name "Net-(U2-RDCM)") (class "Default")
      (node (ref "RDCM1") (pin "1") (pinfunction "1_1") (pintype "passive"))
      (node (ref "U2") (pin "8") (pinfunction "RDCM_8") (pintype "input"))
    )
    (net (code "43") (name "Net-(U2-RVOUT)") (class "Default")
      (node (ref "RVOUT1") (pin "1") (pinfunction "1_1") (pintype "passive"))
      (node (ref "U2") (pin "9") (pinfunction "RVOUT_9") (pintype "output"))
    )
    (net (code "44") (name "Net-(U2-SOURCE)") (class "Default")
      (node (ref "C6") (pin "1") (pinfunction "1_1") (pintype "passive"))
      (node (ref "RPI5") (pin "2") (pinfunction "2_2") (pintype "passive"))
      (node (ref "U2") (pin "6") (pinfunction "SOURCE_6") (pintype "input"))
    )
    (net (code "45") (name "Net-(U3-1A)") (class "Default")
      (node (ref "C15") (pin "2") (pinfunction "2_2") (pintype "passive"))
      (node (ref "FERRITE1") (pin "2") (pinfunction "2_2") (pintype "passive"))
      (node (ref "U3") (pin "P$1") (pinfunction "1A_P$1") (pintype "bidirectional"))
    )
    (net (code "46") (name "Net-(U3-1Y)") (class "Default")
      (node (ref "U3") (pin "P$3") (pinfunction "2A_P$3") (pintype "bidirectional"))
      (node (ref "U3") (pin "P$6") (pinfunction "1Y_P$6") (pintype "bidirectional"))
    )
    (net (code "47") (name "SGND") (class "Default")
      (node (ref "ADUM163N") (pin "8") (pinfunction "GND1_8") (pintype "passive"))
      (node (ref "ISO_IN") (pin "2") (pinfunction "2_2") (pintype "passive"))
      (node (ref "J1") (pin "1") (pinfunction "1_1") (pintype "passive"))
      (node (ref "PD_FI") (pin "1") (pinfunction "1_1") (pintype "passive"))
      (node (ref "PD_II") (pin "1") (pinfunction "1_1") (pintype "passive"))
      (node (ref "PD_MI") (pin "1") (pinfunction "1_1") (pintype "passive"))
    )
    (net (code "48") (name "SMT_OUT") (class "Default")
      (node (ref "ADUM163N") (pin "6") (pinfunction "VOE_6") (pintype "passive"))
      (node (ref "J1") (pin "3") (pinfunction "3_3") (pintype "passive"))
    )
    (net (code "49") (name "VBAT") (class "Default")
      (node (ref "C7") (pin "1") (pinfunction "1_1") (pintype "passive"))
      (node (ref "PWR") (pin "1") (pinfunction "1_1") (pintype "passive"))
      (node (ref "PWR") (pin "4") (pinfunction "4_4") (pintype "passive"))
      (node (ref "PWR") (pin "5") (pinfunction "5_5") (pintype "passive"))
      (node (ref "PWR") (pin "8") (pinfunction "8_8") (pintype "passive"))
      (node (ref "U$4") (pin "1") (pinfunction "P$1_1") (pintype "bidirectional"))
      (node (ref "U$7") (pin "1") (pinfunction "P$1_1") (pintype "bidirectional"))
      (node (ref "U$8") (pin "1") (pinfunction "P$1_1") (pintype "bidirectional"))
    )
    (net (code "50") (name "VLDO") (class "Default")
      (node (ref "ADUM163N") (pin "16") (pinfunction "VDD2_16") (pintype "passive"))
      (node (ref "C12") (pin "A") (pinfunction "+_A") (pintype "passive"))
      (node (ref "C159") (pin "2") (pinfunction "2_2") (pintype "passive"))
      (node (ref "C3") (pin "1") (pinfunction "1_1") (pintype "passive"))
      (node (ref "C5") (pin "2") (pinfunction "2_2") (pintype "passive"))
      (node (ref "C56") (pin "1") (pinfunction "1_1") (pintype "passive"))
      (node (ref "ISO_OUT") (pin "1") (pinfunction "1_1") (pintype "passive"))
      (node (ref "LDO") (pin "P$5") (pinfunction "OUT_P$5") (pintype "bidirectional"))
      (node (ref "R!DONE") (pin "2") (pinfunction "2_2") (pintype "passive"))
      (node (ref "R!DONE1") (pin "1") (pinfunction "1_1") (pintype "passive"))
      (node (ref "U3") (pin "P$5") (pinfunction "VCC_P$5") (pintype "bidirectional"))
    )
    (net (code "51") (name "VSIG") (class "Default")
      (node (ref "ADUM163N") (pin "1") (pinfunction "VDD1_1") (pintype "passive"))
      (node (ref "ISO_IN") (pin "1") (pinfunction "1_1") (pintype "passive"))
      (node (ref "J1") (pin "8") (pinfunction "8_8") (pintype "passive"))
    )
    (net (code "52") (name "VTRANS_PWR") (class "Default")
      (node (ref "C157") (pin "1") (pinfunction "1_1") (pintype "passive"))
      (node (ref "C158") (pin "1") (pinfunction "1_1") (pintype "passive"))
      (node (ref "C4") (pin "1") (pinfunction "1_1") (pintype "passive"))
      (node (ref "C9") (pin "1") (pinfunction "1_1") (pintype "passive"))
      (node (ref "C_TRANS") (pin "1") (pinfunction "1_1") (pintype "passive"))
      (node (ref "C_TRANS1") (pin "1") (pinfunction "1_1") (pintype "passive"))
      (node (ref "C_VCC1") (pin "1") (pinfunction "1_1") (pintype "passive"))
      (node (ref "C_VCC2") (pin "1") (pinfunction "1_1") (pintype "passive"))
      (node (ref "LDO") (pin "P$1") (pinfunction "IN_P$1") (pintype "bidirectional"))
      (node (ref "LDO") (pin "P$3") (pinfunction "EN_P$3") (pintype "bidirectional"))
      (node (ref "LED!DONE") (pin "A") (pinfunction "A_A") (pintype "passive"))
      (node (ref "LED!DONE1") (pin "A") (pinfunction "A_A") (pintype "passive"))
      (node (ref "U$1") (pin "P$3") (pinfunction "P$3_P$3") (pintype "bidirectional"))
      (node (ref "U$1") (pin "P$4") (pinfunction "P$4_P$4") (pintype "bidirectional"))
      (node (ref "U$1") (pin "P$5") (pinfunction "P$5_P$5") (pintype "bidirectional"))
      (node (ref "U$1") (pin "P$6") (pinfunction "P$6_P$6") (pintype "bidirectional"))
      (node (ref "U$10") (pin "POS") (pinfunction "POS_POS") (pintype "bidirectional"))
      (node (ref "U$11") (pin "POS") (pinfunction "POS_POS") (pintype "bidirectional"))
      (node (ref "U$12") (pin "POS") (pinfunction "POS_POS") (pintype "bidirectional"))
      (node (ref "U$13") (pin "POS") (pinfunction "POS_POS") (pintype "bidirectional"))
      (node (ref "U$2") (pin "P$3") (pinfunction "P$3_P$3") (pintype "bidirectional"))
      (node (ref "U$2") (pin "P$4") (pinfunction "P$4_P$4") (pintype "bidirectional"))
      (node (ref "U$2") (pin "P$5") (pinfunction "P$5_P$5") (pintype "bidirectional"))
      (node (ref "U$2") (pin "P$6") (pinfunction "P$6_P$6") (pintype "bidirectional"))
      (node (ref "U$4") (pin "2") (pinfunction "P$2_2") (pintype "bidirectional"))
      (node (ref "U$7") (pin "2") (pinfunction "P$2_2") (pintype "bidirectional"))
      (node (ref "U$8") (pin "2") (pinfunction "P$2_2") (pintype "bidirectional"))
      (node (ref "U1") (pin "1") (pinfunction "VTRANS_1") (pintype "power_in"))
      (node (ref "U1") (pin "4") (pinfunction "VCC_4") (pintype "power_in"))
      (node (ref "U2") (pin "1") (pinfunction "VTRANS_1") (pintype "power_in"))
      (node (ref "U2") (pin "4") (pinfunction "VCC_4") (pintype "power_in"))
      (node (ref "U4") (pin "P$1") (pinfunction "VS_P$1") (pintype "bidirectional"))
      (node (ref "U4") (pin "P$8") (pinfunction "VS2_P$8") (pintype "bidirectional"))
    )
    (net (code "53") (name "unconnected-(U$1-PadP$2)") (class "Default")
      (node (ref "U$1") (pin "P$2") (pinfunction "P$2_P$2") (pintype "bidirectional"))
    )
    (net (code "54") (name "unconnected-(U$1-PadP$11)") (class "Default")
      (node (ref "U$1") (pin "P$11") (pinfunction "P$11_P$11") (pintype "bidirectional"))
    )
    (net (code "55") (name "unconnected-(U$2-PadP$2)") (class "Default")
      (node (ref "U$2") (pin "P$2") (pinfunction "P$2_P$2") (pintype "bidirectional"))
    )
    (net (code "56") (name "unconnected-(U$2-PadP$11)") (class "Default")
      (node (ref "U$2") (pin "P$11") (pinfunction "P$11_P$11") (pintype "bidirectional"))
    )
    (net (code "57") (name "unconnected-(U4-NC-PadP$3)") (class "Default")
      (node (ref "U4") (pin "P$3") (pinfunction "NC_P$3") (pintype "bidirectional"))
    )
  )
)
